# au6850_mp3.net
KiCad netlist of a schematic drawn in EAGLE
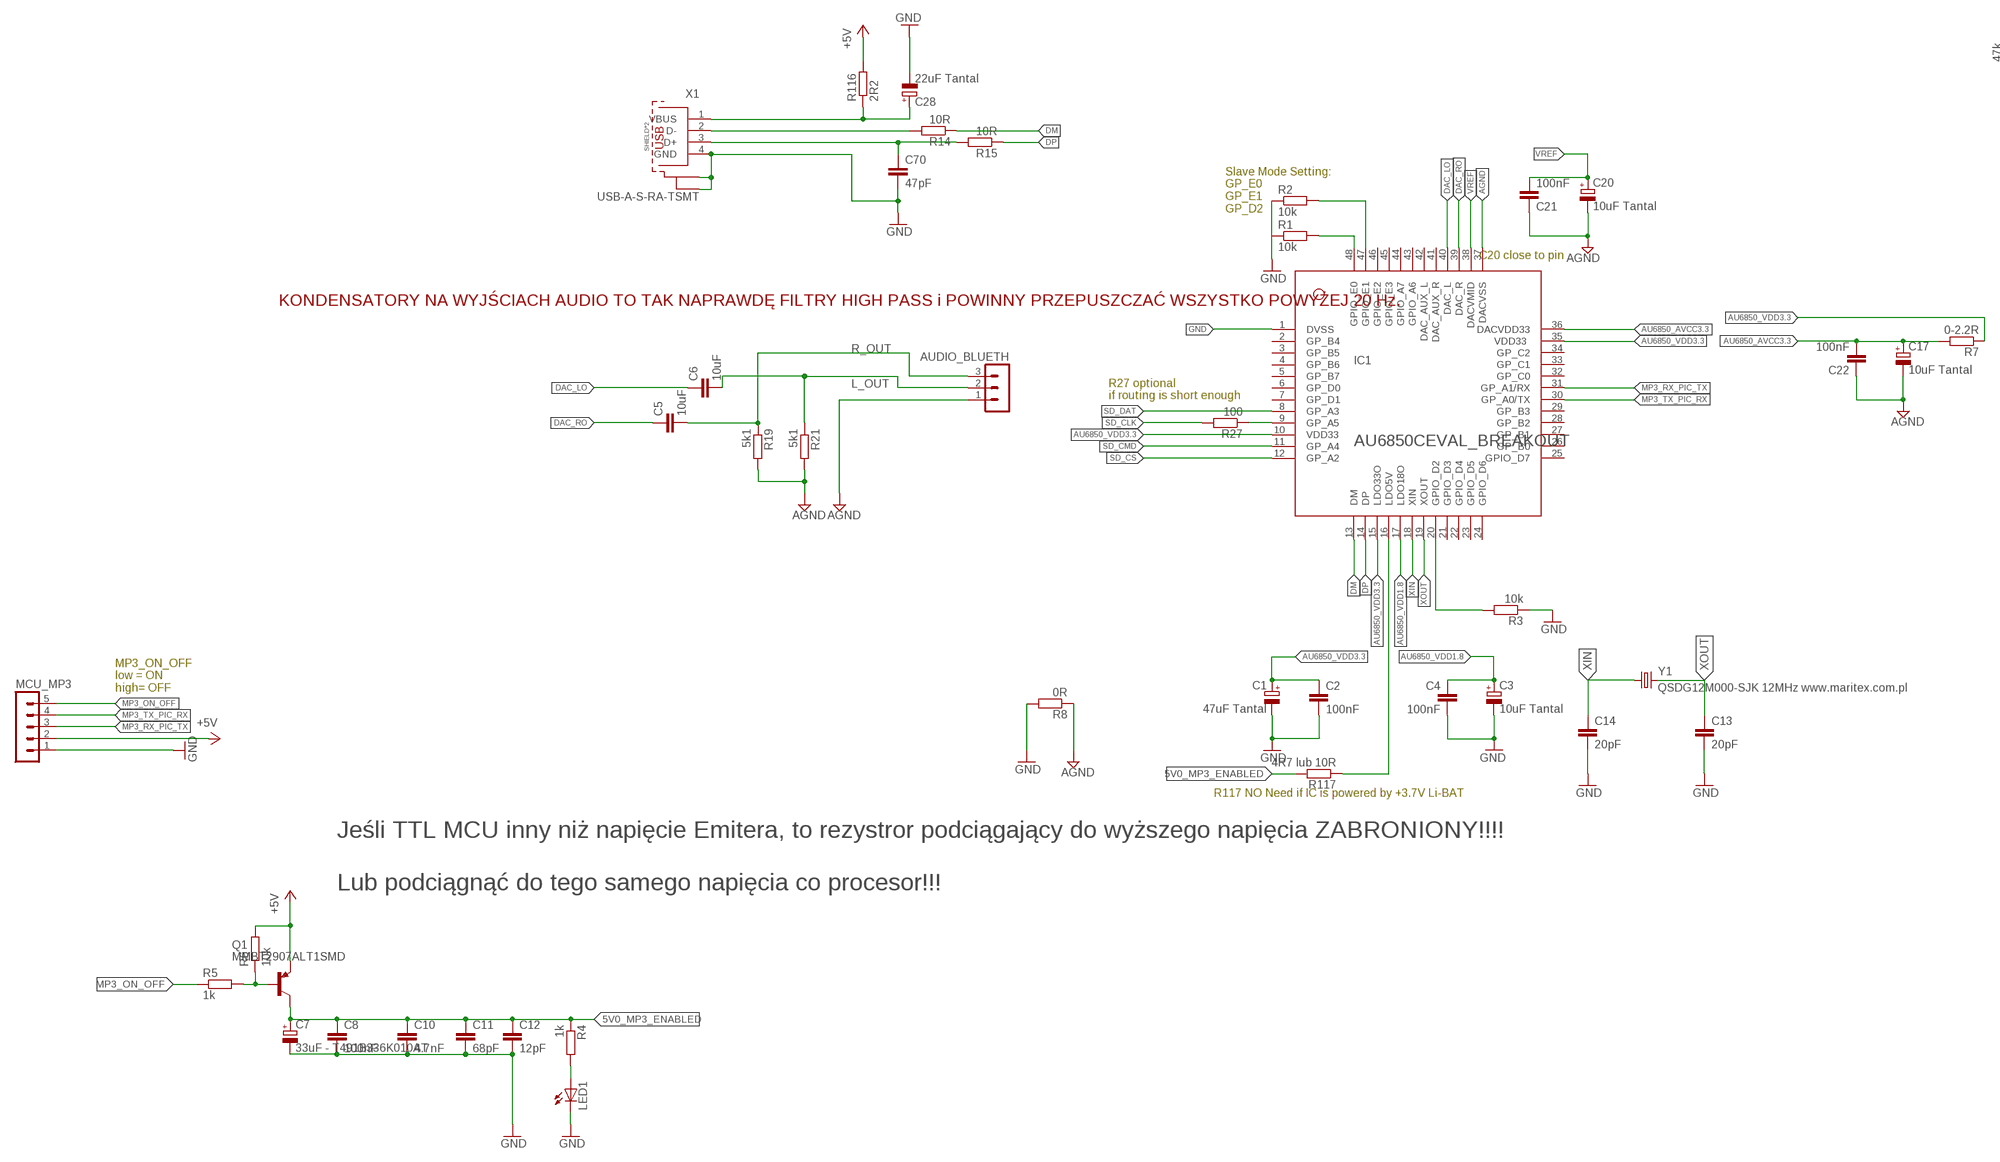
[diagram p0: schematic, sheet 1, part 1 of 2]
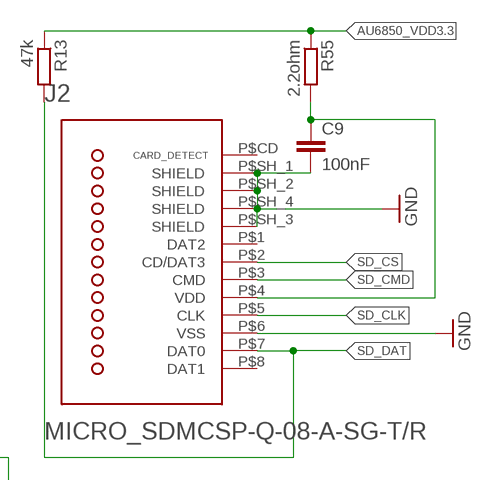
[diagram p1: schematic, sheet 1, part 2 of 2]

(export (version "E")
  (design (tool "Eeschema 10.0.6"))
  (components
    (comp (ref "AUDIO_BLUETH")
      (value "MA03-1")
      (footprint "eagle-import:MA03-1")
      (libsource (lib "eagle-import") (part "MA03-1"))
    )
    (comp (ref "C1")
      (value "47uF Tantal")
      (footprint "eagle-import:B_3528-21R")
      (fields (field (name "PARTNUM") "TAJB476K010R") (field (name "SUPPLIER") "TME"))
      (libsource (lib "eagle-import") (part "CPOL-EUB/3528-21R"))
    )
    (comp (ref "C2")
      (value "100nF")
      (footprint "eagle-import:C0805")
      (libsource (lib "eagle-import") (part "C-EUC0805"))
    )
    (comp (ref "C3")
      (value "10uF Tantal")
      (footprint "eagle-import:B_3528-21R")
      (fields (field (name "PARTNUM") "TAJA106K010R") (field (name "SUPPLIER") "TME"))
      (libsource (lib "eagle-import") (part "CPOL-EUB/3528-21R"))
    )
    (comp (ref "C4")
      (value "100nF")
      (footprint "eagle-import:C0805")
      (libsource (lib "eagle-import") (part "C-EUC0805"))
    )
    (comp (ref "C5")
      (value "10uF")
      (footprint "eagle-import:C0805")
      (libsource (lib "eagle-import") (part "C-EUC0805"))
    )
    (comp (ref "C6")
      (value "10uF")
      (footprint "eagle-import:C0805")
      (libsource (lib "eagle-import") (part "C-EUC0805"))
    )
    (comp (ref "C7")
      (value "33uF - T491B336K010AT")
      (footprint "eagle-import:SMC_B")
      (fields (field (name "PARTNUM") "TAJB336K010R") (field (name "SUPPLIER") "TME"))
      (libsource (lib "eagle-import") (part "resistor_CPOL-EUSMCB"))
    )
    (comp (ref "C8")
      (value "100nF")
      (footprint "eagle-import:C0805")
      (libsource (lib "eagle-import") (part "resistor_C-EUC0805"))
    )
    (comp (ref "C9")
      (value "100nF")
      (footprint "eagle-import:C0805")
      (libsource (lib "eagle-import") (part "resistor_C-EUC0805"))
    )
    (comp (ref "C10")
      (value "4.7nF")
      (footprint "eagle-import:C0805")
      (libsource (lib "eagle-import") (part "resistor_C-EUC0805"))
    )
    (comp (ref "C11")
      (value "68pF")
      (footprint "eagle-import:C0805")
      (libsource (lib "eagle-import") (part "resistor_C-EUC0805"))
    )
    (comp (ref "C12")
      (value "12pF")
      (footprint "eagle-import:C0603K")
      (libsource (lib "eagle-import") (part "resistor_C-EUC0603K"))
    )
    (comp (ref "C13")
      (value "20pF")
      (footprint "eagle-import:C0805")
      (libsource (lib "eagle-import") (part "resistor_C-EUC0805"))
    )
    (comp (ref "C14")
      (value "20pF")
      (footprint "eagle-import:C0805")
      (libsource (lib "eagle-import") (part "resistor_C-EUC0805"))
    )
    (comp (ref "C17")
      (value "10uF Tantal")
      (footprint "eagle-import:B_3528-21R")
      (libsource (lib "eagle-import") (part "CPOL-EUB/3528-21R"))
    )
    (comp (ref "C20")
      (value "10uF Tantal")
      (footprint "eagle-import:B_3528-21R")
      (libsource (lib "eagle-import") (part "CPOL-EUB/3528-21R"))
    )
    (comp (ref "C21")
      (value "100nF")
      (footprint "eagle-import:C0805")
      (libsource (lib "eagle-import") (part "C-EUC0805"))
    )
    (comp (ref "C22")
      (value "100nF")
      (footprint "eagle-import:C0805")
      (libsource (lib "eagle-import") (part "C-EUC0805"))
    )
    (comp (ref "C28")
      (value "22uF Tantal")
      (footprint "eagle-import:SMC_B")
      (fields (field (name "PARTNUM") "TAJB226M010R"))
      (libsource (lib "eagle-import") (part "CPOL-EUSMCB"))
    )
    (comp (ref "C70")
      (value "47pF")
      (footprint "eagle-import:C0805")
      (libsource (lib "eagle-import") (part "resistor_C-EUC0805"))
    )
    (comp (ref "IC1")
      (value "AU6850CEVAL_BREAKOUT")
      (footprint "eagle-import:LQFP48-7BREAKOUT")
      (libsource (lib "eagle-import") (part "AU6850CEVAL_BREAKOUT"))
    )
    (comp (ref "J2")
      (value "MICRO_SDMCSP-Q-08-A-SG-T/R")
      (footprint "eagle-import:MICRO_SD_8PINS")
      (fields (field (name "PARTNUM") "MCSP-Q-08-A-SG-T/R"))
      (libsource (lib "eagle-import") (part "MICRO_SDMCSP-Q-08-A-SG-T/R"))
    )
    (comp (ref "LED1")
      (value "LED3MM")
      (footprint "eagle-import:LED3MM")
      (libsource (lib "eagle-import") (part "LED3MM"))
    )
    (comp (ref "MCU_MP3")
      (value "MA05-1")
      (footprint "eagle-import:MA05-1")
      (libsource (lib "eagle-import") (part "MA05-1"))
    )
    (comp (ref "Q1")
      (value "MMBT2907ALT1SMD")
      (footprint "eagle-import:SOT23-BEC")
      (libsource (lib "eagle-import") (part "MMBT2907SMDALT1"))
    )
    (comp (ref "R1")
      (value "10k")
      (footprint "eagle-import:R0805")
      (libsource (lib "eagle-import") (part "R-EU_R0805"))
    )
    (comp (ref "R2")
      (value "10k")
      (footprint "eagle-import:R0805")
      (libsource (lib "eagle-import") (part "R-EU_R0805"))
    )
    (comp (ref "R3")
      (value "10k")
      (footprint "eagle-import:R0805")
      (libsource (lib "eagle-import") (part "R-EU_R0805"))
    )
    (comp (ref "R4")
      (value "1k")
      (footprint "eagle-import:M0805")
      (libsource (lib "eagle-import") (part "R-EU_M0805"))
    )
    (comp (ref "R5")
      (value "1k")
      (footprint "eagle-import:M0805")
      (libsource (lib "eagle-import") (part "R-EU_M0805"))
    )
    (comp (ref "R6")
      (value "10k")
      (footprint "eagle-import:M0805")
      (libsource (lib "eagle-import") (part "R-EU_M0805"))
    )
    (comp (ref "R7")
      (value "0-2.2R")
      (footprint "eagle-import:R0805")
      (libsource (lib "eagle-import") (part "R-EU_R0805"))
    )
    (comp (ref "R8")
      (value "0R")
      (footprint "eagle-import:R0805")
      (libsource (lib "eagle-import") (part "R-EU_R0805"))
    )
    (comp (ref "R13")
      (value "47k")
      (footprint "eagle-import:R0805")
      (libsource (lib "eagle-import") (part "R-EU_R0805"))
    )
    (comp (ref "R14")
      (value "10R")
      (footprint "eagle-import:R0805")
      (libsource (lib "eagle-import") (part "R-EU_R0805"))
    )
    (comp (ref "R15")
      (value "10R")
      (footprint "eagle-import:R0805")
      (libsource (lib "eagle-import") (part "R-EU_R0805"))
    )
    (comp (ref "R19")
      (value "5k1")
      (footprint "eagle-import:R0805")
      (libsource (lib "eagle-import") (part "R-EU_R0805"))
    )
    (comp (ref "R21")
      (value "5k1")
      (footprint "eagle-import:R0805")
      (libsource (lib "eagle-import") (part "R-EU_R0805"))
    )
    (comp (ref "R27")
      (value "100")
      (footprint "eagle-import:R0805")
      (libsource (lib "eagle-import") (part "R-EU_R0805"))
    )
    (comp (ref "R55")
      (value "2.2ohm")
      (footprint "eagle-import:R0805")
      (libsource (lib "eagle-import") (part "R-EU_R0805"))
    )
    (comp (ref "R116")
      (value "2R2")
      (footprint "eagle-import:R0805")
      (libsource (lib "eagle-import") (part "R-EU_R0805"))
    )
    (comp (ref "R117")
      (value "4R7 lub 10R")
      (footprint "eagle-import:R0805")
      (libsource (lib "eagle-import") (part "R-EU_R0805"))
    )
    (comp (ref "X1")
      (value "USB-A-S-RA-TSMT")
      (footprint "eagle-import:USB-A-S-RA-TSMT")
      (libsource (lib "eagle-import") (part "USB-A-S-RA-TSMT"))
    )
    (comp (ref "Y1")
      (value "QSDG12M000-SJK 12MHz www.maritex.com.pl")
      (footprint "eagle-import:HC49UP")
      (fields (field (name "PARTNUM") "12.00M-SMDHC49S"))
      (libsource (lib "eagle-import") (part "CRYSTALSMD"))
    )
  )
  (nets
    (net (code "1") (name "+5V") (class "Default")
      (node (ref "MCU_MP3") (pin "2") (pinfunction "2_2") (pintype "passive"))
      (node (ref "Q1") (pin "E") (pinfunction "E_E") (pintype "passive"))
      (node (ref "R116") (pin "2") (pinfunction "2_2") (pintype "passive"))
      (node (ref "R6") (pin "2") (pinfunction "2_2") (pintype "passive"))
    )
    (net (code "2") (name "/L_OUT") (class "Default")
      (node (ref "AUDIO_BLUETH") (pin "2") (pinfunction "2_2") (pintype "passive"))
      (node (ref "C6") (pin "2") (pinfunction "2_2") (pintype "passive"))
      (node (ref "R21") (pin "1") (pinfunction "1_1") (pintype "passive"))
    )
    (net (code "3") (name "/R_OUT") (class "Default")
      (node (ref "AUDIO_BLUETH") (pin "3") (pinfunction "3_3") (pintype "passive"))
      (node (ref "C5") (pin "2") (pinfunction "2_2") (pintype "passive"))
      (node (ref "R19") (pin "1") (pinfunction "1_1") (pintype "passive"))
    )
    (net (code "4") (name "5V0_MP3_ENABLED") (class "Default")
      (node (ref "C10") (pin "1") (pinfunction "1_1") (pintype "passive"))
      (node (ref "C11") (pin "1") (pinfunction "1_1") (pintype "passive"))
      (node (ref "C12") (pin "1") (pinfunction "1_1") (pintype "passive"))
      (node (ref "C7") (pin "+") (pinfunction "+_+") (pintype "passive"))
      (node (ref "C8") (pin "1") (pinfunction "1_1") (pintype "passive"))
      (node (ref "Q1") (pin "C") (pinfunction "C_C") (pintype "passive"))
      (node (ref "R117") (pin "2") (pinfunction "2_2") (pintype "passive"))
      (node (ref "R4") (pin "1") (pinfunction "1_1") (pintype "passive"))
    )
    (net (code "5") (name "AGND") (class "Default")
      (node (ref "AUDIO_BLUETH") (pin "1") (pinfunction "1_1") (pintype "passive"))
      (node (ref "C17") (pin "-") (pinfunction "-_-") (pintype "passive"))
      (node (ref "C20") (pin "-") (pinfunction "-_-") (pintype "passive"))
      (node (ref "C21") (pin "1") (pinfunction "1_1") (pintype "passive"))
      (node (ref "C22") (pin "1") (pinfunction "1_1") (pintype "passive"))
      (node (ref "IC1") (pin "37") (pinfunction "DACVSS_37") (pintype "input"))
      (node (ref "R19") (pin "2") (pinfunction "2_2") (pintype "passive"))
      (node (ref "R21") (pin "2") (pinfunction "2_2") (pintype "passive"))
      (node (ref "R8") (pin "1") (pinfunction "1_1") (pintype "passive"))
    )
    (net (code "6") (name "AU6850_AVCC3.3") (class "Default")
      (node (ref "C17") (pin "+") (pinfunction "+_+") (pintype "passive"))
      (node (ref "C22") (pin "2") (pinfunction "2_2") (pintype "passive"))
      (node (ref "IC1") (pin "36") (pinfunction "DACVDD33_36") (pintype "input"))
      (node (ref "R7") (pin "2") (pinfunction "2_2") (pintype "passive"))
    )
    (net (code "7") (name "AU6850_VDD1.8") (class "Default")
      (node (ref "C3") (pin "+") (pinfunction "+_+") (pintype "passive"))
      (node (ref "C4") (pin "1") (pinfunction "1_1") (pintype "passive"))
      (node (ref "IC1") (pin "17") (pinfunction "LDO18O_17") (pintype "bidirectional"))
    )
    (net (code "8") (name "AU6850_VDD3.3") (class "Default")
      (node (ref "C1") (pin "+") (pinfunction "+_+") (pintype "passive"))
      (node (ref "C2") (pin "1") (pinfunction "1_1") (pintype "passive"))
      (node (ref "IC1") (pin "10") (pinfunction "VDD33_10") (pintype "power_in"))
      (node (ref "IC1") (pin "15") (pinfunction "LDO33O_15") (pintype "output"))
      (node (ref "IC1") (pin "35") (pinfunction "VDD33_35") (pintype "input"))
      (node (ref "R13") (pin "1") (pinfunction "1_1") (pintype "passive"))
      (node (ref "R55") (pin "1") (pinfunction "1_1") (pintype "passive"))
      (node (ref "R7") (pin "1") (pinfunction "1_1") (pintype "passive"))
    )
    (net (code "9") (name "DAC_LO") (class "Default")
      (node (ref "C6") (pin "1") (pinfunction "1_1") (pintype "passive"))
      (node (ref "IC1") (pin "40") (pinfunction "DAC_L_40") (pintype "output"))
    )
    (net (code "10") (name "DAC_RO") (class "Default")
      (node (ref "C5") (pin "1") (pinfunction "1_1") (pintype "passive"))
      (node (ref "IC1") (pin "39") (pinfunction "DAC_R_39") (pintype "output"))
    )
    (net (code "11") (name "DM") (class "Default")
      (node (ref "IC1") (pin "13") (pinfunction "DM_13") (pintype "bidirectional"))
      (node (ref "R14") (pin "1") (pinfunction "1_1") (pintype "passive"))
    )
    (net (code "12") (name "DP") (class "Default")
      (node (ref "IC1") (pin "14") (pinfunction "DP_14") (pintype "bidirectional"))
      (node (ref "R15") (pin "1") (pinfunction "1_1") (pintype "passive"))
    )
    (net (code "13") (name "GND") (class "Default")
      (node (ref "C1") (pin "-") (pinfunction "-_-") (pintype "passive"))
      (node (ref "C10") (pin "2") (pinfunction "2_2") (pintype "passive"))
      (node (ref "C11") (pin "2") (pinfunction "2_2") (pintype "passive"))
      (node (ref "C12") (pin "2") (pinfunction "2_2") (pintype "passive"))
      (node (ref "C13") (pin "2") (pinfunction "2_2") (pintype "passive"))
      (node (ref "C14") (pin "2") (pinfunction "2_2") (pintype "passive"))
      (node (ref "C2") (pin "2") (pinfunction "2_2") (pintype "passive"))
      (node (ref "C28") (pin "-") (pinfunction "-_-") (pintype "passive"))
      (node (ref "C3") (pin "-") (pinfunction "-_-") (pintype "passive"))
      (node (ref "C4") (pin "2") (pinfunction "2_2") (pintype "passive"))
      (node (ref "C7") (pin "-") (pinfunction "-_-") (pintype "passive"))
      (node (ref "C70") (pin "2") (pinfunction "2_2") (pintype "passive"))
      (node (ref "C8") (pin "2") (pinfunction "2_2") (pintype "passive"))
      (node (ref "C9") (pin "2") (pinfunction "2_2") (pintype "passive"))
      (node (ref "IC1") (pin "1") (pinfunction "DVSS_1") (pintype "bidirectional"))
      (node (ref "J2") (pin "P$6") (pinfunction "VSS_P$6") (pintype "bidirectional"))
      (node (ref "J2") (pin "P$SH_1") (pinfunction "1_GND_PAD_P$SH_1") (pintype "bidirectional"))
      (node (ref "J2") (pin "P$SH_2") (pinfunction "2_GND_PAD_P$SH_2") (pintype "bidirectional"))
      (node (ref "J2") (pin "P$SH_3") (pinfunction "3_GND_PAD_P$SH_3") (pintype "bidirectional"))
      (node (ref "J2") (pin "P$SH_4") (pinfunction "4_GND_PAD_P$SH_4") (pintype "bidirectional"))
      (node (ref "LED1") (pin "K") (pinfunction "C_K") (pintype "passive"))
      (node (ref "MCU_MP3") (pin "1") (pinfunction "1_1") (pintype "passive"))
      (node (ref "R1") (pin "1") (pinfunction "1_1") (pintype "passive"))
      (node (ref "R2") (pin "1") (pinfunction "1_1") (pintype "passive"))
      (node (ref "R3") (pin "1") (pinfunction "1_1") (pintype "passive"))
      (node (ref "R8") (pin "2") (pinfunction "2_2") (pintype "passive"))
      (node (ref "X1") (pin "4") (pinfunction "GND_4") (pintype "power_in"))
      (node (ref "X1") (pin "5") (pinfunction "SH1_5") (pintype "power_in"))
      (node (ref "X1") (pin "6") (pinfunction "SH2_6") (pintype "power_in"))
    )
    (net (code "14") (name "MP3_ON_OFF") (class "Default")
      (node (ref "MCU_MP3") (pin "5") (pinfunction "5_5") (pintype "passive"))
      (node (ref "R5") (pin "1") (pinfunction "1_1") (pintype "passive"))
    )
    (net (code "15") (name "MP3_RX_PIC_TX") (class "Default")
      (node (ref "IC1") (pin "31") (pinfunction "GP_A1/RX_31") (pintype "bidirectional"))
      (node (ref "MCU_MP3") (pin "3") (pinfunction "3_3") (pintype "passive"))
    )
    (net (code "16") (name "MP3_TX_PIC_RX") (class "Default")
      (node (ref "IC1") (pin "30") (pinfunction "GP_A0/TX_30") (pintype "bidirectional"))
      (node (ref "MCU_MP3") (pin "4") (pinfunction "4_4") (pintype "passive"))
    )
    (net (code "17") (name "Net-(IC1-GPIO_D2)") (class "Default")
      (node (ref "IC1") (pin "20") (pinfunction "GPIO_D2_20") (pintype "bidirectional"))
      (node (ref "R3") (pin "2") (pinfunction "2_2") (pintype "passive"))
    )
    (net (code "18") (name "Net-(IC1-GPIO_E0)") (class "Default")
      (node (ref "IC1") (pin "48") (pinfunction "GPIO_E0_48") (pintype "bidirectional"))
      (node (ref "R1") (pin "2") (pinfunction "2_2") (pintype "passive"))
    )
    (net (code "19") (name "Net-(IC1-GPIO_E1)") (class "Default")
      (node (ref "IC1") (pin "47") (pinfunction "GPIO_E1_47") (pintype "bidirectional"))
      (node (ref "R2") (pin "2") (pinfunction "2_2") (pintype "passive"))
    )
    (net (code "20") (name "Net-(IC1-GP_A5)") (class "Default")
      (node (ref "IC1") (pin "9") (pinfunction "GP_A5_9") (pintype "bidirectional"))
      (node (ref "R27") (pin "1") (pinfunction "1_1") (pintype "passive"))
    )
    (net (code "21") (name "Net-(IC1-LDO5V)") (class "Default")
      (node (ref "IC1") (pin "16") (pinfunction "LDO5V_16") (pintype "bidirectional"))
      (node (ref "R117") (pin "1") (pinfunction "1_1") (pintype "passive"))
    )
    (net (code "22") (name "Net-(J2-VDD)") (class "Default")
      (node (ref "C9") (pin "1") (pinfunction "1_1") (pintype "passive"))
      (node (ref "J2") (pin "P$4") (pinfunction "VDD_P$4") (pintype "bidirectional"))
      (node (ref "R55") (pin "2") (pinfunction "2_2") (pintype "passive"))
    )
    (net (code "23") (name "Net-(LED1-PadA)") (class "Default")
      (node (ref "LED1") (pin "A") (pinfunction "A_A") (pintype "passive"))
      (node (ref "R4") (pin "2") (pinfunction "2_2") (pintype "passive"))
    )
    (net (code "24") (name "Net-(Q1-PadB)") (class "Default")
      (node (ref "Q1") (pin "B") (pinfunction "B_B") (pintype "passive"))
      (node (ref "R5") (pin "2") (pinfunction "2_2") (pintype "passive"))
      (node (ref "R6") (pin "1") (pinfunction "1_1") (pintype "passive"))
    )
    (net (code "25") (name "Net-(X1-D+)") (class "Default")
      (node (ref "C70") (pin "1") (pinfunction "1_1") (pintype "passive"))
      (node (ref "R15") (pin "2") (pinfunction "2_2") (pintype "passive"))
      (node (ref "X1") (pin "3") (pinfunction "D+_3") (pintype "bidirectional"))
    )
    (net (code "26") (name "Net-(X1-D-)") (class "Default")
      (node (ref "R14") (pin "2") (pinfunction "2_2") (pintype "passive"))
      (node (ref "X1") (pin "2") (pinfunction "D-_2") (pintype "bidirectional"))
    )
    (net (code "27") (name "Net-(X1-VBUS)") (class "Default")
      (node (ref "C28") (pin "+") (pinfunction "+_+") (pintype "passive"))
      (node (ref "R116") (pin "1") (pinfunction "1_1") (pintype "passive"))
      (node (ref "X1") (pin "1") (pinfunction "VBUS_1") (pintype "power_in"))
    )
    (net (code "28") (name "SD_CLK") (class "Default")
      (node (ref "J2") (pin "P$5") (pinfunction "CLK_P$5") (pintype "bidirectional"))
      (node (ref "R27") (pin "2") (pinfunction "2_2") (pintype "passive"))
    )
    (net (code "29") (name "SD_CMD") (class "Default")
      (node (ref "IC1") (pin "11") (pinfunction "GP_A4_11") (pintype "bidirectional"))
      (node (ref "J2") (pin "P$3") (pinfunction "CMD_P$3") (pintype "bidirectional"))
    )
    (net (code "30") (name "SD_CS") (class "Default")
      (node (ref "IC1") (pin "12") (pinfunction "GP_A2_12") (pintype "bidirectional"))
      (node (ref "J2") (pin "P$2") (pinfunction "CD/DAT3_P$2") (pintype "bidirectional"))
    )
    (net (code "31") (name "SD_DAT") (class "Default")
      (node (ref "IC1") (pin "8") (pinfunction "GP_A3_8") (pintype "bidirectional"))
      (node (ref "J2") (pin "P$7") (pinfunction "DAT0_P$7") (pintype "bidirectional"))
      (node (ref "R13") (pin "2") (pinfunction "2_2") (pintype "passive"))
    )
    (net (code "32") (name "VREF") (class "Default")
      (node (ref "C20") (pin "+") (pinfunction "+_+") (pintype "passive"))
      (node (ref "C21") (pin "2") (pinfunction "2_2") (pintype "passive"))
      (node (ref "IC1") (pin "38") (pinfunction "DACVMID_38") (pintype "input"))
    )
    (net (code "33") (name "XIN") (class "Default")
      (node (ref "C14") (pin "1") (pinfunction "1_1") (pintype "passive"))
      (node (ref "IC1") (pin "18") (pinfunction "XIN_18") (pintype "input"))
      (node (ref "Y1") (pin "1") (pinfunction "1_1") (pintype "passive"))
    )
    (net (code "34") (name "XOUT") (class "Default")
      (node (ref "C13") (pin "1") (pinfunction "1_1") (pintype "passive"))
      (node (ref "IC1") (pin "19") (pinfunction "XOUT_19") (pintype "output"))
      (node (ref "Y1") (pin "2") (pinfunction "2_2") (pintype "passive"))
    )
    (net (code "35") (name "unconnected-(IC1-DAC_AUX_L-Pad42)") (class "Default")
      (node (ref "IC1") (pin "42") (pinfunction "DAC_AUX_L_42") (pintype "input"))
    )
    (net (code "36") (name "unconnected-(IC1-DAC_AUX_R-Pad41)") (class "Default")
      (node (ref "IC1") (pin "41") (pinfunction "DAC_AUX_R_41") (pintype "input"))
    )
    (net (code "37") (name "unconnected-(IC1-GPIO_A6-Pad43)") (class "Default")
      (node (ref "IC1") (pin "43") (pinfunction "GPIO_A6_43") (pintype "bidirectional"))
    )
    (net (code "38") (name "unconnected-(IC1-GPIO_A7-Pad44)") (class "Default")
      (node (ref "IC1") (pin "44") (pinfunction "GPIO_A7_44") (pintype "bidirectional"))
    )
    (net (code "39") (name "unconnected-(IC1-GPIO_D3-Pad21)") (class "Default")
      (node (ref "IC1") (pin "21") (pinfunction "GPIO_D3_21") (pintype "bidirectional"))
    )
    (net (code "40") (name "unconnected-(IC1-GPIO_D4-Pad22)") (class "Default")
      (node (ref "IC1") (pin "22") (pinfunction "GPIO_D4_22") (pintype "bidirectional"))
    )
    (net (code "41") (name "unconnected-(IC1-GPIO_D5-Pad23)") (class "Default")
      (node (ref "IC1") (pin "23") (pinfunction "GPIO_D5_23") (pintype "bidirectional"))
    )
    (net (code "42") (name "unconnected-(IC1-GPIO_D6-Pad24)") (class "Default")
      (node (ref "IC1") (pin "24") (pinfunction "GPIO_D6_24") (pintype "bidirectional"))
    )
    (net (code "43") (name "unconnected-(IC1-GPIO_D7-Pad25)") (class "Default")
      (node (ref "IC1") (pin "25") (pinfunction "GPIO_D7_25") (pintype "bidirectional"))
    )
    (net (code "44") (name "unconnected-(IC1-GPIO_E2-Pad46)") (class "Default")
      (node (ref "IC1") (pin "46") (pinfunction "GPIO_E2_46") (pintype "bidirectional"))
    )
    (net (code "45") (name "unconnected-(IC1-GPIO_E3-Pad45)") (class "Default")
      (node (ref "IC1") (pin "45") (pinfunction "GPIO_E3_45") (pintype "bidirectional"))
    )
    (net (code "46") (name "unconnected-(IC1-GP_B0-Pad26)") (class "Default")
      (node (ref "IC1") (pin "26") (pinfunction "GP_B0_26") (pintype "bidirectional"))
    )
    (net (code "47") (name "unconnected-(IC1-GP_B1-Pad27)") (class "Default")
      (node (ref "IC1") (pin "27") (pinfunction "GP_B1_27") (pintype "bidirectional"))
    )
    (net (code "48") (name "unconnected-(IC1-GP_B2-Pad28)") (class "Default")
      (node (ref "IC1") (pin "28") (pinfunction "GP_B2_28") (pintype "bidirectional"))
    )
    (net (code "49") (name "unconnected-(IC1-GP_B3-Pad29)") (class "Default")
      (node (ref "IC1") (pin "29") (pinfunction "GP_B3_29") (pintype "bidirectional"))
    )
    (net (code "50") (name "unconnected-(IC1-GP_B4-Pad2)") (class "Default")
      (node (ref "IC1") (pin "2") (pinfunction "GP_B4_2") (pintype "bidirectional"))
    )
    (net (code "51") (name "unconnected-(IC1-GP_B5-Pad3)") (class "Default")
      (node (ref "IC1") (pin "3") (pinfunction "GP_B5_3") (pintype "bidirectional"))
    )
    (net (code "52") (name "unconnected-(IC1-GP_B6-Pad4)") (class "Default")
      (node (ref "IC1") (pin "4") (pinfunction "GP_B6_4") (pintype "bidirectional"))
    )
    (net (code "53") (name "unconnected-(IC1-GP_B7-Pad5)") (class "Default")
      (node (ref "IC1") (pin "5") (pinfunction "GP_B7_5") (pintype "bidirectional"))
    )
    (net (code "54") (name "unconnected-(IC1-GP_C0-Pad32)") (class "Default")
      (node (ref "IC1") (pin "32") (pinfunction "GP_C0_32") (pintype "bidirectional"))
    )
    (net (code "55") (name "unconnected-(IC1-GP_C1-Pad33)") (class "Default")
      (node (ref "IC1") (pin "33") (pinfunction "GP_C1_33") (pintype "bidirectional"))
    )
    (net (code "56") (name "unconnected-(IC1-GP_C2-Pad34)") (class "Default")
      (node (ref "IC1") (pin "34") (pinfunction "GP_C2_34") (pintype "bidirectional"))
    )
    (net (code "57") (name "unconnected-(IC1-GP_D0-Pad6)") (class "Default")
      (node (ref "IC1") (pin "6") (pinfunction "GP_D0_6") (pintype "bidirectional"))
    )
    (net (code "58") (name "unconnected-(IC1-GP_D1-Pad7)") (class "Default")
      (node (ref "IC1") (pin "7") (pinfunction "GP_D1_7") (pintype "bidirectional"))
    )
    (net (code "59") (name "unconnected-(J2-CARD_DETECT_SW-PadP$CD)") (class "Default")
      (node (ref "J2") (pin "P$CD") (pinfunction "CARD_DETECT_SW_P$CD") (pintype "bidirectional"))
    )
    (net (code "60") (name "unconnected-(J2-DAT1-PadP$8)") (class "Default")
      (node (ref "J2") (pin "P$8") (pinfunction "DAT1_P$8") (pintype "bidirectional"))
    )
    (net (code "61") (name "unconnected-(J2-DAT2-PadP$1)") (class "Default")
      (node (ref "J2") (pin "P$1") (pinfunction "DAT2_P$1") (pintype "bidirectional"))
    )
  )
)
